# pot-boardDesp.net
KiCad netlist of a schematic drawn in EAGLE
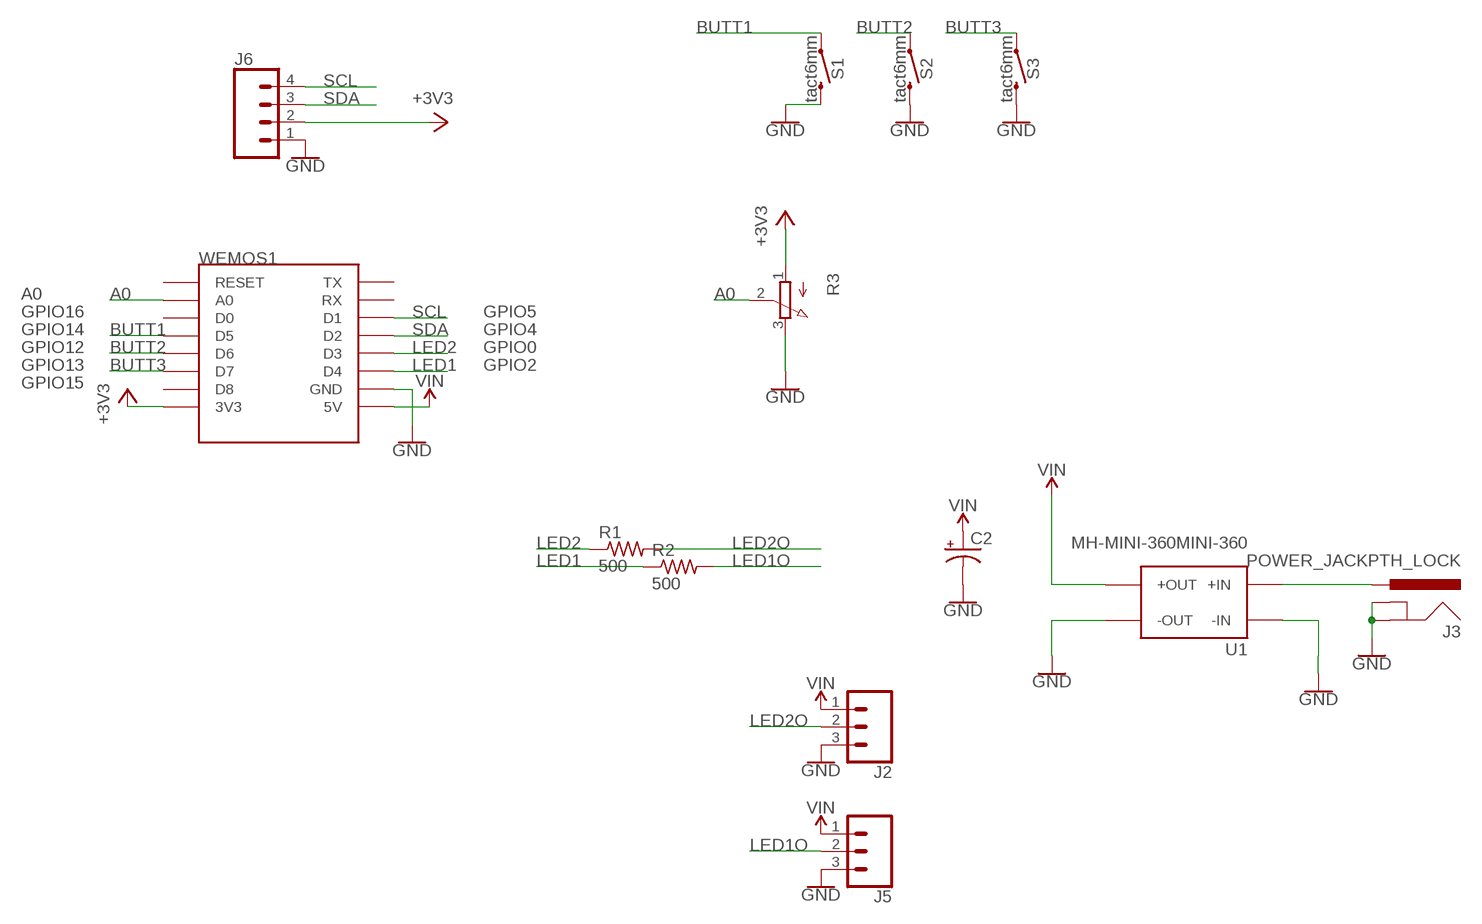
[diagram p0: schematic, sheet 1]

(export (version "E")
  (design (tool "Eeschema 10.0.6"))
  (components
    (comp (ref "C2")
      (value "CPOL-USE3.5-8")
      (footprint "eagle-import:E3,5-8")
      (libsource (lib "eagle-import") (part "CPOL-USE3.5-8"))
    )
    (comp (ref "J2")
      (value "CONN_03")
      (footprint "eagle-import:1X03")
      (libsource (lib "eagle-import") (part "CONN_03"))
    )
    (comp (ref "J3")
      (value "POWER_JACKPTH_LOCK")
      (footprint "eagle-import:POWER_JACK_PTH_LOCK")
      (libsource (lib "eagle-import") (part "POWER_JACKPTH_LOCK"))
    )
    (comp (ref "J5")
      (value "CONN_03")
      (footprint "eagle-import:1X03")
      (libsource (lib "eagle-import") (part "CONN_03"))
    )
    (comp (ref "J6")
      (value "CONN_04")
      (footprint "eagle-import:1X04")
      (libsource (lib "eagle-import") (part "CONN_04"))
    )
    (comp (ref "R1")
      (value "500")
      (footprint "eagle-import:R0805")
      (libsource (lib "eagle-import") (part "R-US_R0805"))
    )
    (comp (ref "R2")
      (value "500")
      (footprint "eagle-import:R0805")
      (libsource (lib "eagle-import") (part "R-US_R0805"))
    )
    (comp (ref "R3")
      (value "3RP/1610N")
      (footprint "eagle-import:3RP_1610N")
      (libsource (lib "eagle-import") (part "3RP/1610N"))
    )
    (comp (ref "S1")
      (value "tact6mm")
      (footprint "eagle-import:TACTILE_SWITCH_PTH_6.0MM")
      (libsource (lib "eagle-import") (part "MOMENTARY-SWITCH-SPST-PTH-6.0MM"))
    )
    (comp (ref "S2")
      (value "tact6mm")
      (footprint "eagle-import:TACTILE_SWITCH_PTH_6.0MM")
      (libsource (lib "eagle-import") (part "MOMENTARY-SWITCH-SPST-PTH-6.0MM"))
    )
    (comp (ref "S3")
      (value "tact6mm")
      (footprint "eagle-import:TACTILE_SWITCH_PTH_6.0MM")
      (libsource (lib "eagle-import") (part "MOMENTARY-SWITCH-SPST-PTH-6.0MM"))
    )
    (comp (ref "U1")
      (value "MH-MINI-360MINI-360")
      (footprint "eagle-import:MH-MINI-360")
      (libsource (lib "eagle-import") (part "MH-MINI-360MINI-360"))
    )
    (comp (ref "WEMOS1")
      (value "WEMOS-D1-MINI")
      (footprint "eagle-import:WEMOS-D1-MINI")
      (libsource (lib "eagle-import") (part "WEMOS-D1-MINI"))
    )
  )
  (nets
    (net (code "1") (name "+3V3") (class "Default")
      (node (ref "J6") (pin "2") (pinfunction "2_2") (pintype "passive"))
      (node (ref "R3") (pin "1") (pinfunction "A_1") (pintype "passive"))
      (node (ref "WEMOS1") (pin "3V3") (pinfunction "3V3_3V3") (pintype "bidirectional"))
    )
    (net (code "2") (name "/A0") (class "Default")
      (node (ref "R3") (pin "2") (pinfunction "S_2") (pintype "passive"))
      (node (ref "WEMOS1") (pin "A0") (pinfunction "A0_A0") (pintype "bidirectional"))
    )
    (net (code "3") (name "/BUTT1") (class "Default")
      (node (ref "S1") (pin "1") (pinfunction "1_1") (pintype "passive"))
      (node (ref "WEMOS1") (pin "D5") (pinfunction "D5_D5") (pintype "bidirectional"))
    )
    (net (code "4") (name "/BUTT2") (class "Default")
      (node (ref "S2") (pin "1") (pinfunction "1_1") (pintype "passive"))
      (node (ref "WEMOS1") (pin "D6") (pinfunction "D6_D6") (pintype "bidirectional"))
    )
    (net (code "5") (name "/BUTT3") (class "Default")
      (node (ref "S3") (pin "1") (pinfunction "1_1") (pintype "passive"))
      (node (ref "WEMOS1") (pin "D7") (pinfunction "D7_D7") (pintype "bidirectional"))
    )
    (net (code "6") (name "/LED1") (class "Default")
      (node (ref "R2") (pin "1") (pinfunction "1_1") (pintype "passive"))
      (node (ref "WEMOS1") (pin "D4") (pinfunction "D4_D4") (pintype "bidirectional"))
    )
    (net (code "7") (name "/LED1O") (class "Default")
      (node (ref "J5") (pin "2") (pinfunction "2_2") (pintype "passive"))
      (node (ref "R2") (pin "2") (pinfunction "2_2") (pintype "passive"))
    )
    (net (code "8") (name "/LED2") (class "Default")
      (node (ref "R1") (pin "1") (pinfunction "1_1") (pintype "passive"))
      (node (ref "WEMOS1") (pin "D3") (pinfunction "D3_D3") (pintype "bidirectional"))
    )
    (net (code "9") (name "/LED2O") (class "Default")
      (node (ref "J2") (pin "2") (pinfunction "2_2") (pintype "passive"))
      (node (ref "R1") (pin "2") (pinfunction "2_2") (pintype "passive"))
    )
    (net (code "10") (name "/SCL") (class "Default")
      (node (ref "J6") (pin "4") (pinfunction "4_4") (pintype "passive"))
      (node (ref "WEMOS1") (pin "D1") (pinfunction "D1_D1") (pintype "bidirectional"))
    )
    (net (code "11") (name "/SDA") (class "Default")
      (node (ref "J6") (pin "3") (pinfunction "3_3") (pintype "passive"))
      (node (ref "WEMOS1") (pin "D2") (pinfunction "D2_D2") (pintype "bidirectional"))
    )
    (net (code "12") (name "GND") (class "Default")
      (node (ref "C2") (pin "-") (pinfunction "-_-") (pintype "passive"))
      (node (ref "J2") (pin "3") (pinfunction "3_3") (pintype "passive"))
      (node (ref "J3") (pin "GND") (pinfunction "GND_GND") (pintype "bidirectional"))
      (node (ref "J3") (pin "GNDBREAK") (pinfunction "GNDBREAK_GNDBREAK") (pintype "bidirectional"))
      (node (ref "J5") (pin "3") (pinfunction "3_3") (pintype "passive"))
      (node (ref "J6") (pin "1") (pinfunction "1_1") (pintype "passive"))
      (node (ref "R3") (pin "3") (pinfunction "E_3") (pintype "passive"))
      (node (ref "S1") (pin "3") (pinfunction "2_3") (pintype "passive"))
      (node (ref "S2") (pin "3") (pinfunction "2_3") (pintype "passive"))
      (node (ref "S3") (pin "3") (pinfunction "2_3") (pintype "passive"))
      (node (ref "U1") (pin "P$1") (pinfunction "-IN_P$1") (pintype "power_in"))
      (node (ref "U1") (pin "P$4") (pinfunction "-OUT_P$4") (pintype "power_in"))
      (node (ref "WEMOS1") (pin "GND") (pinfunction "GND_GND") (pintype "bidirectional"))
    )
    (net (code "13") (name "Net-(U1-+IN)") (class "Default")
      (node (ref "J3") (pin "PWR") (pinfunction "PWR_PWR") (pintype "bidirectional"))
      (node (ref "U1") (pin "P$2") (pinfunction "+IN_P$2") (pintype "power_in"))
    )
    (net (code "14") (name "VIN") (class "Default")
      (node (ref "C2") (pin "+") (pinfunction "+_+") (pintype "passive"))
      (node (ref "J2") (pin "1") (pinfunction "1_1") (pintype "passive"))
      (node (ref "J5") (pin "1") (pinfunction "1_1") (pintype "passive"))
      (node (ref "U1") (pin "P$3") (pinfunction "+OUT_P$3") (pintype "power_in"))
      (node (ref "WEMOS1") (pin "5V") (pinfunction "5V_5V") (pintype "bidirectional"))
    )
    (net (code "15") (name "unconnected-(WEMOS1-PadD0)") (class "Default")
      (node (ref "WEMOS1") (pin "D0") (pinfunction "D0_D0") (pintype "bidirectional"))
    )
    (net (code "16") (name "unconnected-(WEMOS1-PadD8)") (class "Default")
      (node (ref "WEMOS1") (pin "D8") (pinfunction "D8_D8") (pintype "bidirectional"))
    )
    (net (code "17") (name "unconnected-(WEMOS1-PadRESET)") (class "Default")
      (node (ref "WEMOS1") (pin "RESET") (pinfunction "RESET_RESET") (pintype "bidirectional"))
    )
    (net (code "18") (name "unconnected-(WEMOS1-PadRX)") (class "Default")
      (node (ref "WEMOS1") (pin "RX") (pinfunction "RX_RX") (pintype "bidirectional"))
    )
    (net (code "19") (name "unconnected-(WEMOS1-PadTX)") (class "Default")
      (node (ref "WEMOS1") (pin "TX") (pinfunction "TX_TX") (pintype "bidirectional"))
    )
  )
)
